# Emotion.net
KiCad netlist of a schematic drawn in EAGLE
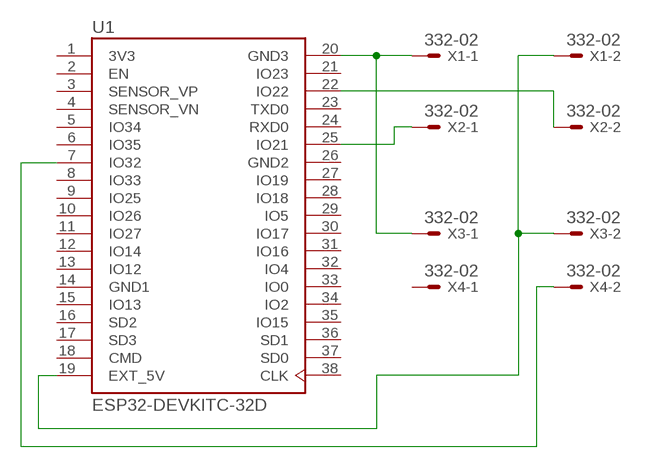
[diagram p0: schematic, sheet 1]

(export (version "E")
  (design (tool "Eeschema 10.0.6"))
  (components
    (comp (ref "U1")
      (value "ESP32-DEVKITC-32D")
      (footprint "eagle-import:MODULE_ESP32-DEVKITC-32D")
      (fields (field (name "MF") "Espressif Systems"))
      (libsource (lib "eagle-import") (part "ESP32-DEVKITC-32D"))
    )
    (comp (ref "X1")
      (value "332-02")
      (footprint "eagle-import:332-02")
      (libsource (lib "eagle-import") (part "332-02"))
    )
    (comp (ref "X2")
      (value "332-02")
      (footprint "eagle-import:332-02")
      (libsource (lib "eagle-import") (part "332-02"))
    )
    (comp (ref "X3")
      (value "332-02")
      (footprint "eagle-import:332-02")
      (libsource (lib "eagle-import") (part "332-02"))
    )
    (comp (ref "X4")
      (value "332-02")
      (footprint "eagle-import:332-02")
      (libsource (lib "eagle-import") (part "332-02"))
    )
  )
  (nets
    (net (code "1") (name "/3V3") (class "Default")
      (node (ref "U1") (pin "1") (pinfunction "3V3_1") (pintype "power_in"))
    )
    (net (code "2") (name "/GND1") (class "Default")
      (node (ref "U1") (pin "14") (pinfunction "GND1_14") (pintype "power_in"))
    )
    (net (code "3") (name "/GND2") (class "Default")
      (node (ref "U1") (pin "26") (pinfunction "GND2_26") (pintype "power_in"))
    )
    (net (code "4") (name "Net-(U1-EXT_5V)") (class "Default")
      (node (ref "U1") (pin "19") (pinfunction "EXT_5V_19") (pintype "power_in"))
      (node (ref "X1") (pin "2") (pinfunction "S_2") (pintype "passive"))
      (node (ref "X3") (pin "2") (pinfunction "S_2") (pintype "passive"))
    )
    (net (code "5") (name "Net-(U1-GND3)") (class "Default")
      (node (ref "U1") (pin "20") (pinfunction "GND3_20") (pintype "power_in"))
      (node (ref "X1") (pin "1") (pinfunction "S_1") (pintype "passive"))
      (node (ref "X3") (pin "1") (pinfunction "S_1") (pintype "passive"))
    )
    (net (code "6") (name "Net-(U1-IO21)") (class "Default")
      (node (ref "U1") (pin "25") (pinfunction "IO21_25") (pintype "bidirectional"))
      (node (ref "X2") (pin "1") (pinfunction "S_1") (pintype "passive"))
    )
    (net (code "7") (name "Net-(U1-IO22)") (class "Default")
      (node (ref "U1") (pin "22") (pinfunction "IO22_22") (pintype "bidirectional"))
      (node (ref "X2") (pin "2") (pinfunction "S_2") (pintype "passive"))
    )
    (net (code "8") (name "Net-(U1-IO32)") (class "Default")
      (node (ref "U1") (pin "7") (pinfunction "IO32_7") (pintype "bidirectional"))
      (node (ref "X4") (pin "2") (pinfunction "S_2") (pintype "passive"))
    )
    (net (code "9") (name "unconnected-(U1-CLK-Pad38)") (class "Default")
      (node (ref "U1") (pin "38") (pinfunction "CLK_38") (pintype "input"))
    )
    (net (code "10") (name "unconnected-(U1-CMD-Pad18)") (class "Default")
      (node (ref "U1") (pin "18") (pinfunction "CMD_18") (pintype "bidirectional"))
    )
    (net (code "11") (name "unconnected-(U1-EN-Pad2)") (class "Default")
      (node (ref "U1") (pin "2") (pinfunction "EN_2") (pintype "input"))
    )
    (net (code "12") (name "unconnected-(U1-IO0-Pad33)") (class "Default")
      (node (ref "U1") (pin "33") (pinfunction "IO0_33") (pintype "bidirectional"))
    )
    (net (code "13") (name "unconnected-(U1-IO2-Pad34)") (class "Default")
      (node (ref "U1") (pin "34") (pinfunction "IO2_34") (pintype "bidirectional"))
    )
    (net (code "14") (name "unconnected-(U1-IO4-Pad32)") (class "Default")
      (node (ref "U1") (pin "32") (pinfunction "IO4_32") (pintype "bidirectional"))
    )
    (net (code "15") (name "unconnected-(U1-IO5-Pad29)") (class "Default")
      (node (ref "U1") (pin "29") (pinfunction "IO5_29") (pintype "bidirectional"))
    )
    (net (code "16") (name "unconnected-(U1-IO12-Pad13)") (class "Default")
      (node (ref "U1") (pin "13") (pinfunction "IO12_13") (pintype "bidirectional"))
    )
    (net (code "17") (name "unconnected-(U1-IO13-Pad15)") (class "Default")
      (node (ref "U1") (pin "15") (pinfunction "IO13_15") (pintype "bidirectional"))
    )
    (net (code "18") (name "unconnected-(U1-IO14-Pad12)") (class "Default")
      (node (ref "U1") (pin "12") (pinfunction "IO14_12") (pintype "bidirectional"))
    )
    (net (code "19") (name "unconnected-(U1-IO15-Pad35)") (class "Default")
      (node (ref "U1") (pin "35") (pinfunction "IO15_35") (pintype "bidirectional"))
    )
    (net (code "20") (name "unconnected-(U1-IO16-Pad31)") (class "Default")
      (node (ref "U1") (pin "31") (pinfunction "IO16_31") (pintype "bidirectional"))
    )
    (net (code "21") (name "unconnected-(U1-IO17-Pad30)") (class "Default")
      (node (ref "U1") (pin "30") (pinfunction "IO17_30") (pintype "bidirectional"))
    )
    (net (code "22") (name "unconnected-(U1-IO18-Pad28)") (class "Default")
      (node (ref "U1") (pin "28") (pinfunction "IO18_28") (pintype "bidirectional"))
    )
    (net (code "23") (name "unconnected-(U1-IO19-Pad27)") (class "Default")
      (node (ref "U1") (pin "27") (pinfunction "IO19_27") (pintype "bidirectional"))
    )
    (net (code "24") (name "unconnected-(U1-IO23-Pad21)") (class "Default")
      (node (ref "U1") (pin "21") (pinfunction "IO23_21") (pintype "bidirectional"))
    )
    (net (code "25") (name "unconnected-(U1-IO25-Pad9)") (class "Default")
      (node (ref "U1") (pin "9") (pinfunction "IO25_9") (pintype "bidirectional"))
    )
    (net (code "26") (name "unconnected-(U1-IO26-Pad10)") (class "Default")
      (node (ref "U1") (pin "10") (pinfunction "IO26_10") (pintype "bidirectional"))
    )
    (net (code "27") (name "unconnected-(U1-IO27-Pad11)") (class "Default")
      (node (ref "U1") (pin "11") (pinfunction "IO27_11") (pintype "bidirectional"))
    )
    (net (code "28") (name "unconnected-(U1-IO33-Pad8)") (class "Default")
      (node (ref "U1") (pin "8") (pinfunction "IO33_8") (pintype "bidirectional"))
    )
    (net (code "29") (name "unconnected-(U1-IO34-Pad5)") (class "Default")
      (node (ref "U1") (pin "5") (pinfunction "IO34_5") (pintype "bidirectional"))
    )
    (net (code "30") (name "unconnected-(U1-IO35-Pad6)") (class "Default")
      (node (ref "U1") (pin "6") (pinfunction "IO35_6") (pintype "bidirectional"))
    )
    (net (code "31") (name "unconnected-(U1-RXD0-Pad24)") (class "Default")
      (node (ref "U1") (pin "24") (pinfunction "RXD0_24") (pintype "input"))
    )
    (net (code "32") (name "unconnected-(U1-SD0-Pad37)") (class "Default")
      (node (ref "U1") (pin "37") (pinfunction "SD0_37") (pintype "bidirectional"))
    )
    (net (code "33") (name "unconnected-(U1-SD1-Pad36)") (class "Default")
      (node (ref "U1") (pin "36") (pinfunction "SD1_36") (pintype "bidirectional"))
    )
    (net (code "34") (name "unconnected-(U1-SD2-Pad16)") (class "Default")
      (node (ref "U1") (pin "16") (pinfunction "SD2_16") (pintype "bidirectional"))
    )
    (net (code "35") (name "unconnected-(U1-SD3-Pad17)") (class "Default")
      (node (ref "U1") (pin "17") (pinfunction "SD3_17") (pintype "bidirectional"))
    )
    (net (code "36") (name "unconnected-(U1-SENSOR_VN-Pad4)") (class "Default")
      (node (ref "U1") (pin "4") (pinfunction "SENSOR_VN_4") (pintype "input"))
    )
    (net (code "37") (name "unconnected-(U1-SENSOR_VP-Pad3)") (class "Default")
      (node (ref "U1") (pin "3") (pinfunction "SENSOR_VP_3") (pintype "input"))
    )
    (net (code "38") (name "unconnected-(U1-TXD0-Pad23)") (class "Default")
      (node (ref "U1") (pin "23") (pinfunction "TXD0_23") (pintype "output"))
    )
    (net (code "39") (name "unconnected-(X4A-S-Pad1)") (class "Default")
      (node (ref "X4") (pin "1") (pinfunction "S_1") (pintype "passive"))
    )
  )
)
